# TP1_NodoWiFi_Per_Rev0.net
KiCad netlist of a schematic drawn in Altium Designer
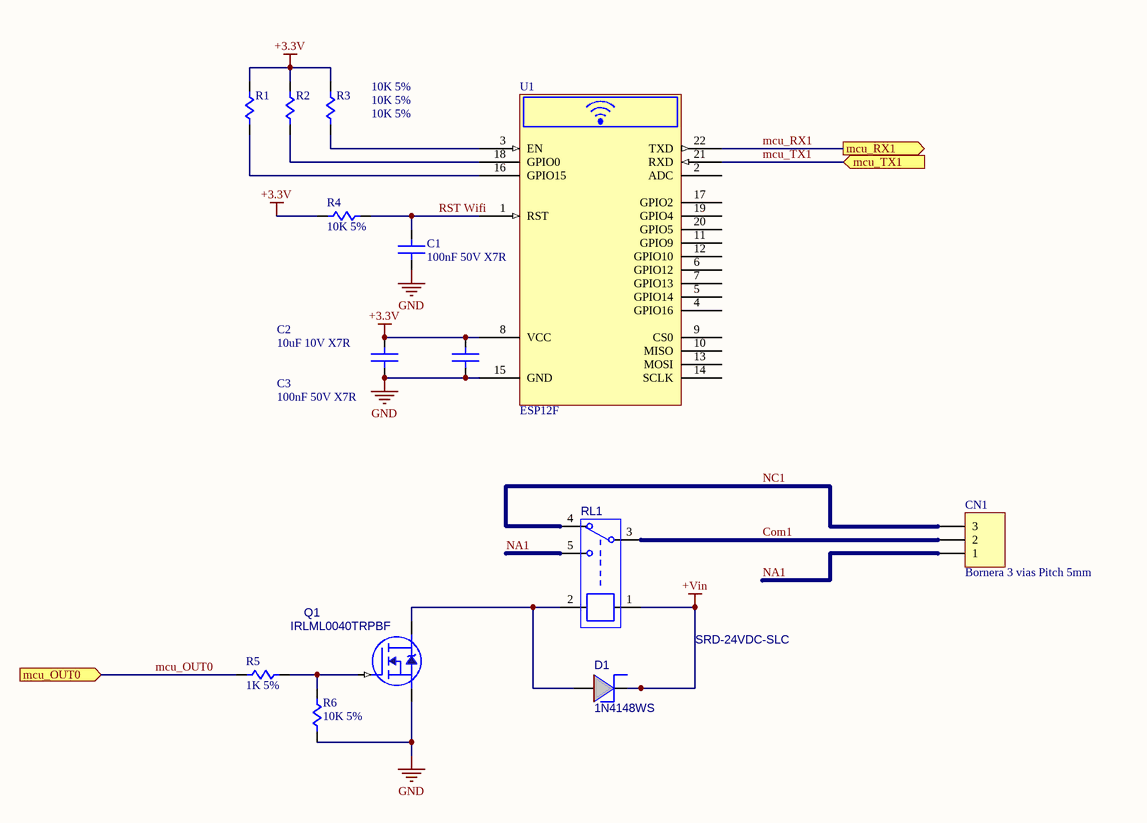
[diagram p0: TP1_NodoWiFi_Per_Rev0.SchDoc]

(export (version "E")
  (design (tool "Eeschema 10.0.6"))
  (components
    (comp (ref "C1")
      (value "100nF 50V X7R")
      (footprint "C_0805")
      (description "capacitor no polarizado")
      (libsource (lib "WifiNode") (part "Capacitor_NoP"))
    )
    (comp (ref "C2")
      (value "10uF 10V X7R")
      (footprint "C_0805")
      (description "capacitor no polarizado")
      (libsource (lib "WifiNode") (part "Capacitor_NoP"))
    )
    (comp (ref "C3")
      (value "100nF 50V X7R")
      (footprint "C_0805")
      (description "capacitor no polarizado")
      (libsource (lib "WifiNode") (part "Capacitor_NoP"))
    )
    (comp (ref "CN1")
      (value "Bornera 3 vias Pitch 5mm")
      (footprint "Terminal Block")
      (description "Connector Generic 3 Vias")
      (libsource (lib "WifiNode") (part "CONN_03P"))
    )
    (comp (ref "D1")
      (value "1N4148WS")
      (description "Diode Shottky")
      (libsource (lib "WifiNode") (part "DIODO_SH"))
    )
    (comp (ref "Q1")
      (value "IRLML0040TRPBF")
      (footprint "IC SOT-23")
      (description "Mosfet N-Ch")
      (libsource (lib "WifiNode") (part "N_MOSFET_SOT23"))
    )
    (comp (ref "R1")
      (value "10K 5%")
      (footprint "R_0805")
      (description "Resistor")
      (libsource (lib "WifiNode") (part "Resistencia"))
    )
    (comp (ref "R2")
      (value "10K 5%")
      (footprint "R_0805")
      (description "Resistor")
      (libsource (lib "WifiNode") (part "Resistencia"))
    )
    (comp (ref "R3")
      (value "10K 5%")
      (footprint "R_0805")
      (description "Resistor")
      (libsource (lib "WifiNode") (part "Resistencia"))
    )
    (comp (ref "R4")
      (value "10K 5%")
      (footprint "R_0805")
      (description "Resistor")
      (libsource (lib "WifiNode") (part "Resistencia"))
    )
    (comp (ref "R5")
      (value "1K 5%")
      (footprint "R_0805")
      (description "Resistor")
      (libsource (lib "WifiNode") (part "Resistencia"))
    )
    (comp (ref "R6")
      (value "10K 5%")
      (footprint "R_0805")
      (description "Resistor")
      (libsource (lib "WifiNode") (part "Resistencia"))
    )
    (comp (ref "RL1")
      (value "SRD-24VDC-SLC")
      (footprint "Relay 24V")
      (description "Relay SPDT")
      (libsource (lib "WifiNode") (part "RELAY SPDT"))
    )
    (comp (ref "U1")
      (value "ESP12F")
      (footprint "ESP12F")
      (description "Wifi Module")
      (libsource (lib "WifiNode") (part "ESP12F Wifi Module"))
    )
  )
  (nets
    (net (code "1") (name "+3.3V") (class "Default")
      (node (ref "C2") (pin "2") (pinfunction "Cap_2") (pintype "passive"))
      (node (ref "C3") (pin "2") (pinfunction "Cap_2") (pintype "passive"))
      (node (ref "R1") (pin "2") (pinfunction "Cap_2") (pintype "passive"))
      (node (ref "R2") (pin "2") (pinfunction "Cap_2") (pintype "passive"))
      (node (ref "R3") (pin "2") (pinfunction "Cap_2") (pintype "passive"))
      (node (ref "R4") (pin "2") (pinfunction "Cap_2") (pintype "passive"))
      (node (ref "U1") (pin "8") (pinfunction "VCC_8") (pintype "power_in"))
    )
    (net (code "2") (name "+Vin") (class "Default")
      (node (ref "D1") (pin "2") (pinfunction "K_2") (pintype "passive"))
      (node (ref "RL1") (pin "1") (pinfunction "1_1") (pintype "passive"))
    )
    (net (code "3") (name "/Com1") (class "Default")
      (node (ref "CN1") (pin "2") (pinfunction "2_2") (pintype "passive"))
      (node (ref "RL1") (pin "3") (pinfunction "3_3") (pintype "passive"))
    )
    (net (code "4") (name "/NA1") (class "Default")
      (node (ref "CN1") (pin "1") (pinfunction "1_1") (pintype "passive"))
      (node (ref "RL1") (pin "5") (pinfunction "5_5") (pintype "passive"))
    )
    (net (code "5") (name "/NC1") (class "Default")
      (node (ref "CN1") (pin "3") (pinfunction "3_3") (pintype "passive"))
      (node (ref "RL1") (pin "4") (pinfunction "4_4") (pintype "passive"))
    )
    (net (code "6") (name "/RST Wifi") (class "Default")
      (node (ref "C1") (pin "2") (pinfunction "Cap_2") (pintype "passive"))
      (node (ref "R4") (pin "1") (pinfunction "Cap_1") (pintype "passive"))
      (node (ref "U1") (pin "1") (pinfunction "RST_1") (pintype "input"))
    )
    (net (code "7") (name "/mcu_OUT0") (class "Default")
      (node (ref "R5") (pin "2") (pinfunction "Cap_2") (pintype "passive"))
    )
    (net (code "8") (name "/mcu_RX1") (class "Default")
      (node (ref "U1") (pin "22") (pinfunction "TXD_22") (pintype "output"))
    )
    (net (code "9") (name "/mcu_TX1") (class "Default")
      (node (ref "U1") (pin "21") (pinfunction "RXD_21") (pintype "input"))
    )
    (net (code "10") (name "GND") (class "Default")
      (node (ref "C1") (pin "1") (pinfunction "Cap_1") (pintype "passive"))
      (node (ref "C2") (pin "1") (pinfunction "Cap_1") (pintype "passive"))
      (node (ref "C3") (pin "1") (pinfunction "Cap_1") (pintype "passive"))
      (node (ref "Q1") (pin "2") (pinfunction "SOURCE_2") (pintype "passive"))
      (node (ref "R6") (pin "1") (pinfunction "Cap_1") (pintype "passive"))
      (node (ref "U1") (pin "15") (pinfunction "GND_15") (pintype "power_in"))
    )
    (net (code "11") (name "Net-(D1-A)") (class "Default")
      (node (ref "D1") (pin "1") (pinfunction "A_1") (pintype "passive"))
      (node (ref "Q1") (pin "3") (pinfunction "DRAIN_3") (pintype "passive"))
      (node (ref "RL1") (pin "2") (pinfunction "2_2") (pintype "passive"))
    )
    (net (code "12") (name "Net-(Q1-GATE)") (class "Default")
      (node (ref "Q1") (pin "1") (pinfunction "GATE_1") (pintype "input"))
      (node (ref "R5") (pin "1") (pinfunction "Cap_1") (pintype "passive"))
      (node (ref "R6") (pin "2") (pinfunction "Cap_2") (pintype "passive"))
    )
    (net (code "13") (name "Net-(U1-EN)") (class "Default")
      (node (ref "R3") (pin "1") (pinfunction "Cap_1") (pintype "passive"))
      (node (ref "U1") (pin "3") (pinfunction "EN_3") (pintype "input"))
    )
    (net (code "14") (name "Net-(U1-GPIO0)") (class "Default")
      (node (ref "R2") (pin "1") (pinfunction "Cap_1") (pintype "passive"))
      (node (ref "U1") (pin "18") (pinfunction "GPIO0_18") (pintype "passive"))
    )
    (net (code "15") (name "Net-(U1-GPIO15)") (class "Default")
      (node (ref "R1") (pin "1") (pinfunction "Cap_1") (pintype "passive"))
      (node (ref "U1") (pin "16") (pinfunction "GPIO15_16") (pintype "passive"))
    )
    (net (code "16") (name "unconnected-(U1-ADC-Pad2)") (class "Default")
      (node (ref "U1") (pin "2") (pinfunction "ADC_2") (pintype "passive"))
    )
    (net (code "17") (name "unconnected-(U1-CS0-Pad9)") (class "Default")
      (node (ref "U1") (pin "9") (pinfunction "CS0_9") (pintype "passive"))
    )
    (net (code "18") (name "unconnected-(U1-GPIO2-Pad17)") (class "Default")
      (node (ref "U1") (pin "17") (pinfunction "GPIO2_17") (pintype "passive"))
    )
    (net (code "19") (name "unconnected-(U1-GPIO4-Pad19)") (class "Default")
      (node (ref "U1") (pin "19") (pinfunction "GPIO4_19") (pintype "passive"))
    )
    (net (code "20") (name "unconnected-(U1-GPIO5-Pad20)") (class "Default")
      (node (ref "U1") (pin "20") (pinfunction "GPIO5_20") (pintype "passive"))
    )
    (net (code "21") (name "unconnected-(U1-GPIO9-Pad11)") (class "Default")
      (node (ref "U1") (pin "11") (pinfunction "GPIO9_11") (pintype "passive"))
    )
    (net (code "22") (name "unconnected-(U1-GPIO10-Pad12)") (class "Default")
      (node (ref "U1") (pin "12") (pinfunction "GPIO10_12") (pintype "passive"))
    )
    (net (code "23") (name "unconnected-(U1-GPIO12-Pad6)") (class "Default")
      (node (ref "U1") (pin "6") (pinfunction "GPIO12_6") (pintype "passive"))
    )
    (net (code "24") (name "unconnected-(U1-GPIO13-Pad7)") (class "Default")
      (node (ref "U1") (pin "7") (pinfunction "GPIO13_7") (pintype "passive"))
    )
    (net (code "25") (name "unconnected-(U1-GPIO14-Pad5)") (class "Default")
      (node (ref "U1") (pin "5") (pinfunction "GPIO14_5") (pintype "passive"))
    )
    (net (code "26") (name "unconnected-(U1-GPIO16-Pad4)") (class "Default")
      (node (ref "U1") (pin "4") (pinfunction "GPIO16_4") (pintype "passive"))
    )
    (net (code "27") (name "unconnected-(U1-MISO-Pad10)") (class "Default")
      (node (ref "U1") (pin "10") (pinfunction "MISO_10") (pintype "passive"))
    )
    (net (code "28") (name "unconnected-(U1-MOSI-Pad13)") (class "Default")
      (node (ref "U1") (pin "13") (pinfunction "MOSI_13") (pintype "passive"))
    )
    (net (code "29") (name "unconnected-(U1-SCLK-Pad14)") (class "Default")
      (node (ref "U1") (pin "14") (pinfunction "SCLK_14") (pintype "passive"))
    )
  )
)
